# SCH_SEGEMENTOS_MINUTERO_2.net
KiCad netlist of a schematic drawn in Altium Designer
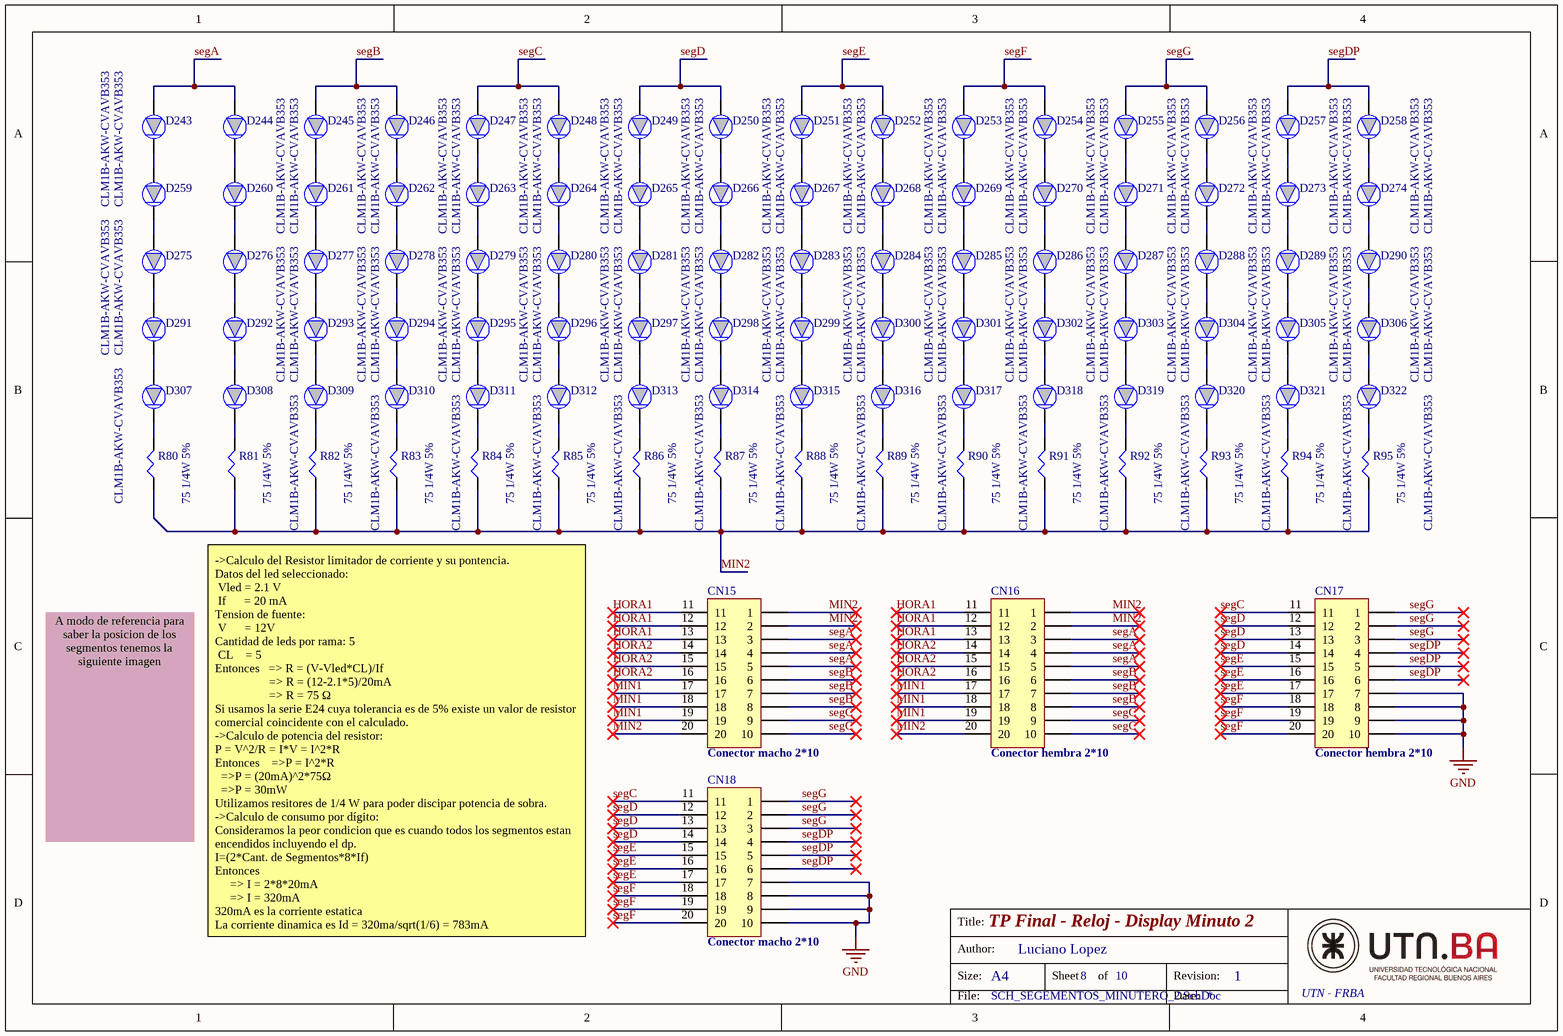
[diagram p0: SCH_SEGEMENTOS_MINUTERO_2.SchDoc]

(export (version "E")
  (design (tool "Eeschema 10.0.6"))
  (components
    (comp (ref "CN15")
      (value "Conector macho 2*10")
      (description "Connector Generic 10 Vias")
      (libsource (lib "SCH_LIB") (part "CONN_2x10P"))
    )
    (comp (ref "CN16")
      (value "Conector hembra 2*10")
      (description "Connector Generic 10 Vias")
      (libsource (lib "SCH_LIB") (part "CONN_2x10P"))
    )
    (comp (ref "CN17")
      (value "Conector hembra 2*10")
      (description "Connector Generic 10 Vias")
      (libsource (lib "SCH_LIB") (part "CONN_2x10P"))
    )
    (comp (ref "CN18")
      (value "Conector macho 2*10")
      (description "Connector Generic 10 Vias")
      (libsource (lib "SCH_LIB") (part "CONN_2x10P"))
    )
    (comp (ref "D243")
      (value "CLM1B-AKW-CVAVB353")
      (footprint "PLCC2_LED")
      (libsource (lib "SCH_LIB") (part "LED_DIODE"))
    )
    (comp (ref "D244")
      (value "CLM1B-AKW-CVAVB353")
      (footprint "PLCC2_LED")
      (libsource (lib "SCH_LIB") (part "LED_DIODE"))
    )
    (comp (ref "D245")
      (value "CLM1B-AKW-CVAVB353")
      (footprint "PLCC2_LED")
      (libsource (lib "SCH_LIB") (part "LED_DIODE"))
    )
    (comp (ref "D246")
      (value "CLM1B-AKW-CVAVB353")
      (footprint "PLCC2_LED")
      (libsource (lib "SCH_LIB") (part "LED_DIODE"))
    )
    (comp (ref "D247")
      (value "CLM1B-AKW-CVAVB353")
      (footprint "PLCC2_LED")
      (libsource (lib "SCH_LIB") (part "LED_DIODE"))
    )
    (comp (ref "D248")
      (value "CLM1B-AKW-CVAVB353")
      (footprint "PLCC2_LED")
      (libsource (lib "SCH_LIB") (part "LED_DIODE"))
    )
    (comp (ref "D249")
      (value "CLM1B-AKW-CVAVB353")
      (footprint "PLCC2_LED")
      (libsource (lib "SCH_LIB") (part "LED_DIODE"))
    )
    (comp (ref "D250")
      (value "CLM1B-AKW-CVAVB353")
      (footprint "PLCC2_LED")
      (libsource (lib "SCH_LIB") (part "LED_DIODE"))
    )
    (comp (ref "D251")
      (value "CLM1B-AKW-CVAVB353")
      (footprint "PLCC2_LED")
      (libsource (lib "SCH_LIB") (part "LED_DIODE"))
    )
    (comp (ref "D252")
      (value "CLM1B-AKW-CVAVB353")
      (footprint "PLCC2_LED")
      (libsource (lib "SCH_LIB") (part "LED_DIODE"))
    )
    (comp (ref "D253")
      (value "CLM1B-AKW-CVAVB353")
      (footprint "PLCC2_LED")
      (libsource (lib "SCH_LIB") (part "LED_DIODE"))
    )
    (comp (ref "D254")
      (value "CLM1B-AKW-CVAVB353")
      (footprint "PLCC2_LED")
      (libsource (lib "SCH_LIB") (part "LED_DIODE"))
    )
    (comp (ref "D255")
      (value "CLM1B-AKW-CVAVB353")
      (footprint "PLCC2_LED")
      (libsource (lib "SCH_LIB") (part "LED_DIODE"))
    )
    (comp (ref "D256")
      (value "CLM1B-AKW-CVAVB353")
      (footprint "PLCC2_LED")
      (libsource (lib "SCH_LIB") (part "LED_DIODE"))
    )
    (comp (ref "D257")
      (value "CLM1B-AKW-CVAVB353")
      (footprint "PLCC2_LED")
      (libsource (lib "SCH_LIB") (part "LED_DIODE"))
    )
    (comp (ref "D258")
      (value "CLM1B-AKW-CVAVB353")
      (footprint "PLCC2_LED")
      (libsource (lib "SCH_LIB") (part "LED_DIODE"))
    )
    (comp (ref "D259")
      (value "CLM1B-AKW-CVAVB353")
      (footprint "PLCC2_LED")
      (libsource (lib "SCH_LIB") (part "LED_DIODE"))
    )
    (comp (ref "D260")
      (value "CLM1B-AKW-CVAVB353")
      (footprint "PLCC2_LED")
      (libsource (lib "SCH_LIB") (part "LED_DIODE"))
    )
    (comp (ref "D261")
      (value "CLM1B-AKW-CVAVB353")
      (footprint "PLCC2_LED")
      (libsource (lib "SCH_LIB") (part "LED_DIODE"))
    )
    (comp (ref "D262")
      (value "CLM1B-AKW-CVAVB353")
      (footprint "PLCC2_LED")
      (libsource (lib "SCH_LIB") (part "LED_DIODE"))
    )
    (comp (ref "D263")
      (value "CLM1B-AKW-CVAVB353")
      (footprint "PLCC2_LED")
      (libsource (lib "SCH_LIB") (part "LED_DIODE"))
    )
    (comp (ref "D264")
      (value "CLM1B-AKW-CVAVB353")
      (footprint "PLCC2_LED")
      (libsource (lib "SCH_LIB") (part "LED_DIODE"))
    )
    (comp (ref "D265")
      (value "CLM1B-AKW-CVAVB353")
      (footprint "PLCC2_LED")
      (libsource (lib "SCH_LIB") (part "LED_DIODE"))
    )
    (comp (ref "D266")
      (value "CLM1B-AKW-CVAVB353")
      (footprint "PLCC2_LED")
      (libsource (lib "SCH_LIB") (part "LED_DIODE"))
    )
    (comp (ref "D267")
      (value "CLM1B-AKW-CVAVB353")
      (footprint "PLCC2_LED")
      (libsource (lib "SCH_LIB") (part "LED_DIODE"))
    )
    (comp (ref "D268")
      (value "CLM1B-AKW-CVAVB353")
      (footprint "PLCC2_LED")
      (libsource (lib "SCH_LIB") (part "LED_DIODE"))
    )
    (comp (ref "D269")
      (value "CLM1B-AKW-CVAVB353")
      (footprint "PLCC2_LED")
      (libsource (lib "SCH_LIB") (part "LED_DIODE"))
    )
    (comp (ref "D270")
      (value "CLM1B-AKW-CVAVB353")
      (footprint "PLCC2_LED")
      (libsource (lib "SCH_LIB") (part "LED_DIODE"))
    )
    (comp (ref "D271")
      (value "CLM1B-AKW-CVAVB353")
      (footprint "PLCC2_LED")
      (libsource (lib "SCH_LIB") (part "LED_DIODE"))
    )
    (comp (ref "D272")
      (value "CLM1B-AKW-CVAVB353")
      (footprint "PLCC2_LED")
      (libsource (lib "SCH_LIB") (part "LED_DIODE"))
    )
    (comp (ref "D273")
      (value "CLM1B-AKW-CVAVB353")
      (footprint "PLCC2_LED")
      (libsource (lib "SCH_LIB") (part "LED_DIODE"))
    )
    (comp (ref "D274")
      (value "CLM1B-AKW-CVAVB353")
      (footprint "PLCC2_LED")
      (libsource (lib "SCH_LIB") (part "LED_DIODE"))
    )
    (comp (ref "D275")
      (value "CLM1B-AKW-CVAVB353")
      (footprint "PLCC2_LED")
      (libsource (lib "SCH_LIB") (part "LED_DIODE"))
    )
    (comp (ref "D276")
      (value "CLM1B-AKW-CVAVB353")
      (footprint "PLCC2_LED")
      (libsource (lib "SCH_LIB") (part "LED_DIODE"))
    )
    (comp (ref "D277")
      (value "CLM1B-AKW-CVAVB353")
      (footprint "PLCC2_LED")
      (libsource (lib "SCH_LIB") (part "LED_DIODE"))
    )
    (comp (ref "D278")
      (value "CLM1B-AKW-CVAVB353")
      (footprint "PLCC2_LED")
      (libsource (lib "SCH_LIB") (part "LED_DIODE"))
    )
    (comp (ref "D279")
      (value "CLM1B-AKW-CVAVB353")
      (footprint "PLCC2_LED")
      (libsource (lib "SCH_LIB") (part "LED_DIODE"))
    )
    (comp (ref "D280")
      (value "CLM1B-AKW-CVAVB353")
      (footprint "PLCC2_LED")
      (libsource (lib "SCH_LIB") (part "LED_DIODE"))
    )
    (comp (ref "D281")
      (value "CLM1B-AKW-CVAVB353")
      (footprint "PLCC2_LED")
      (libsource (lib "SCH_LIB") (part "LED_DIODE"))
    )
    (comp (ref "D282")
      (value "CLM1B-AKW-CVAVB353")
      (footprint "PLCC2_LED")
      (libsource (lib "SCH_LIB") (part "LED_DIODE"))
    )
    (comp (ref "D283")
      (value "CLM1B-AKW-CVAVB353")
      (footprint "PLCC2_LED")
      (libsource (lib "SCH_LIB") (part "LED_DIODE"))
    )
    (comp (ref "D284")
      (value "CLM1B-AKW-CVAVB353")
      (footprint "PLCC2_LED")
      (libsource (lib "SCH_LIB") (part "LED_DIODE"))
    )
    (comp (ref "D285")
      (value "CLM1B-AKW-CVAVB353")
      (footprint "PLCC2_LED")
      (libsource (lib "SCH_LIB") (part "LED_DIODE"))
    )
    (comp (ref "D286")
      (value "CLM1B-AKW-CVAVB353")
      (footprint "PLCC2_LED")
      (libsource (lib "SCH_LIB") (part "LED_DIODE"))
    )
    (comp (ref "D287")
      (value "CLM1B-AKW-CVAVB353")
      (footprint "PLCC2_LED")
      (libsource (lib "SCH_LIB") (part "LED_DIODE"))
    )
    (comp (ref "D288")
      (value "CLM1B-AKW-CVAVB353")
      (footprint "PLCC2_LED")
      (libsource (lib "SCH_LIB") (part "LED_DIODE"))
    )
    (comp (ref "D289")
      (value "CLM1B-AKW-CVAVB353")
      (footprint "PLCC2_LED")
      (libsource (lib "SCH_LIB") (part "LED_DIODE"))
    )
    (comp (ref "D290")
      (value "CLM1B-AKW-CVAVB353")
      (footprint "PLCC2_LED")
      (libsource (lib "SCH_LIB") (part "LED_DIODE"))
    )
    (comp (ref "D291")
      (value "CLM1B-AKW-CVAVB353")
      (footprint "PLCC2_LED")
      (libsource (lib "SCH_LIB") (part "LED_DIODE"))
    )
    (comp (ref "D292")
      (value "CLM1B-AKW-CVAVB353")
      (footprint "PLCC2_LED")
      (libsource (lib "SCH_LIB") (part "LED_DIODE"))
    )
    (comp (ref "D293")
      (value "CLM1B-AKW-CVAVB353")
      (footprint "PLCC2_LED")
      (libsource (lib "SCH_LIB") (part "LED_DIODE"))
    )
    (comp (ref "D294")
      (value "CLM1B-AKW-CVAVB353")
      (footprint "PLCC2_LED")
      (libsource (lib "SCH_LIB") (part "LED_DIODE"))
    )
    (comp (ref "D295")
      (value "CLM1B-AKW-CVAVB353")
      (footprint "PLCC2_LED")
      (libsource (lib "SCH_LIB") (part "LED_DIODE"))
    )
    (comp (ref "D296")
      (value "CLM1B-AKW-CVAVB353")
      (footprint "PLCC2_LED")
      (libsource (lib "SCH_LIB") (part "LED_DIODE"))
    )
    (comp (ref "D297")
      (value "CLM1B-AKW-CVAVB353")
      (footprint "PLCC2_LED")
      (libsource (lib "SCH_LIB") (part "LED_DIODE"))
    )
    (comp (ref "D298")
      (value "CLM1B-AKW-CVAVB353")
      (footprint "PLCC2_LED")
      (libsource (lib "SCH_LIB") (part "LED_DIODE"))
    )
    (comp (ref "D299")
      (value "CLM1B-AKW-CVAVB353")
      (footprint "PLCC2_LED")
      (libsource (lib "SCH_LIB") (part "LED_DIODE"))
    )
    (comp (ref "D300")
      (value "CLM1B-AKW-CVAVB353")
      (footprint "PLCC2_LED")
      (libsource (lib "SCH_LIB") (part "LED_DIODE"))
    )
    (comp (ref "D301")
      (value "CLM1B-AKW-CVAVB353")
      (footprint "PLCC2_LED")
      (libsource (lib "SCH_LIB") (part "LED_DIODE"))
    )
    (comp (ref "D302")
      (value "CLM1B-AKW-CVAVB353")
      (footprint "PLCC2_LED")
      (libsource (lib "SCH_LIB") (part "LED_DIODE"))
    )
    (comp (ref "D303")
      (value "CLM1B-AKW-CVAVB353")
      (footprint "PLCC2_LED")
      (libsource (lib "SCH_LIB") (part "LED_DIODE"))
    )
    (comp (ref "D304")
      (value "CLM1B-AKW-CVAVB353")
      (footprint "PLCC2_LED")
      (libsource (lib "SCH_LIB") (part "LED_DIODE"))
    )
    (comp (ref "D305")
      (value "CLM1B-AKW-CVAVB353")
      (footprint "PLCC2_LED")
      (libsource (lib "SCH_LIB") (part "LED_DIODE"))
    )
    (comp (ref "D306")
      (value "CLM1B-AKW-CVAVB353")
      (footprint "PLCC2_LED")
      (libsource (lib "SCH_LIB") (part "LED_DIODE"))
    )
    (comp (ref "D307")
      (value "CLM1B-AKW-CVAVB353")
      (footprint "PLCC2_LED")
      (libsource (lib "SCH_LIB") (part "LED_DIODE"))
    )
    (comp (ref "D308")
      (value "CLM1B-AKW-CVAVB353")
      (footprint "PLCC2_LED")
      (libsource (lib "SCH_LIB") (part "LED_DIODE"))
    )
    (comp (ref "D309")
      (value "CLM1B-AKW-CVAVB353")
      (footprint "PLCC2_LED")
      (libsource (lib "SCH_LIB") (part "LED_DIODE"))
    )
    (comp (ref "D310")
      (value "CLM1B-AKW-CVAVB353")
      (footprint "PLCC2_LED")
      (libsource (lib "SCH_LIB") (part "LED_DIODE"))
    )
    (comp (ref "D311")
      (value "CLM1B-AKW-CVAVB353")
      (footprint "PLCC2_LED")
      (libsource (lib "SCH_LIB") (part "LED_DIODE"))
    )
    (comp (ref "D312")
      (value "CLM1B-AKW-CVAVB353")
      (footprint "PLCC2_LED")
      (libsource (lib "SCH_LIB") (part "LED_DIODE"))
    )
    (comp (ref "D313")
      (value "CLM1B-AKW-CVAVB353")
      (footprint "PLCC2_LED")
      (libsource (lib "SCH_LIB") (part "LED_DIODE"))
    )
    (comp (ref "D314")
      (value "CLM1B-AKW-CVAVB353")
      (footprint "PLCC2_LED")
      (libsource (lib "SCH_LIB") (part "LED_DIODE"))
    )
    (comp (ref "D315")
      (value "CLM1B-AKW-CVAVB353")
      (footprint "PLCC2_LED")
      (libsource (lib "SCH_LIB") (part "LED_DIODE"))
    )
    (comp (ref "D316")
      (value "CLM1B-AKW-CVAVB353")
      (footprint "PLCC2_LED")
      (libsource (lib "SCH_LIB") (part "LED_DIODE"))
    )
    (comp (ref "D317")
      (value "CLM1B-AKW-CVAVB353")
      (footprint "PLCC2_LED")
      (libsource (lib "SCH_LIB") (part "LED_DIODE"))
    )
    (comp (ref "D318")
      (value "CLM1B-AKW-CVAVB353")
      (footprint "PLCC2_LED")
      (libsource (lib "SCH_LIB") (part "LED_DIODE"))
    )
    (comp (ref "D319")
      (value "CLM1B-AKW-CVAVB353")
      (footprint "PLCC2_LED")
      (libsource (lib "SCH_LIB") (part "LED_DIODE"))
    )
    (comp (ref "D320")
      (value "CLM1B-AKW-CVAVB353")
      (footprint "PLCC2_LED")
      (libsource (lib "SCH_LIB") (part "LED_DIODE"))
    )
    (comp (ref "D321")
      (value "CLM1B-AKW-CVAVB353")
      (footprint "PLCC2_LED")
      (libsource (lib "SCH_LIB") (part "LED_DIODE"))
    )
    (comp (ref "D322")
      (value "CLM1B-AKW-CVAVB353")
      (footprint "PLCC2_LED")
      (libsource (lib "SCH_LIB") (part "LED_DIODE"))
    )
    (comp (ref "R80") (value "75 1/4W 5%") (footprint "R_0805") (libsource (lib "SCH_LIB") (part "Resistor")))
    (comp (ref "R81") (value "75 1/4W 5%") (footprint "R_0805") (libsource (lib "SCH_LIB") (part "Resistor")))
    (comp (ref "R82") (value "75 1/4W 5%") (footprint "R_0805") (libsource (lib "SCH_LIB") (part "Resistor")))
    (comp (ref "R83") (value "75 1/4W 5%") (footprint "R_0805") (libsource (lib "SCH_LIB") (part "Resistor")))
    (comp (ref "R84") (value "75 1/4W 5%") (footprint "R_0805") (libsource (lib "SCH_LIB") (part "Resistor")))
    (comp (ref "R85") (value "75 1/4W 5%") (footprint "R_0805") (libsource (lib "SCH_LIB") (part "Resistor")))
    (comp (ref "R86") (value "75 1/4W 5%") (footprint "R_0805") (libsource (lib "SCH_LIB") (part "Resistor")))
    (comp (ref "R87") (value "75 1/4W 5%") (footprint "R_0805") (libsource (lib "SCH_LIB") (part "Resistor")))
    (comp (ref "R88") (value "75 1/4W 5%") (footprint "R_0805") (libsource (lib "SCH_LIB") (part "Resistor")))
    (comp (ref "R89") (value "75 1/4W 5%") (footprint "R_0805") (libsource (lib "SCH_LIB") (part "Resistor")))
    (comp (ref "R90") (value "75 1/4W 5%") (footprint "R_0805") (libsource (lib "SCH_LIB") (part "Resistor")))
    (comp (ref "R91") (value "75 1/4W 5%") (footprint "R_0805") (libsource (lib "SCH_LIB") (part "Resistor")))
    (comp (ref "R92") (value "75 1/4W 5%") (footprint "R_0805") (libsource (lib "SCH_LIB") (part "Resistor")))
    (comp (ref "R93") (value "75 1/4W 5%") (footprint "R_0805") (libsource (lib "SCH_LIB") (part "Resistor")))
    (comp (ref "R94") (value "75 1/4W 5%") (footprint "R_0805") (libsource (lib "SCH_LIB") (part "Resistor")))
    (comp (ref "R95") (value "75 1/4W 5%") (footprint "R_0805") (libsource (lib "SCH_LIB") (part "Resistor")))
  )
  (nets
    (net (code "1") (name "/HORA1") (class "Default")
      (node (ref "CN15") (pin "11") (pinfunction "11_11") (pintype "passive"))
      (node (ref "CN15") (pin "12") (pinfunction "12_12") (pintype "passive"))
      (node (ref "CN15") (pin "13") (pinfunction "13_13") (pintype "passive"))
      (node (ref "CN16") (pin "11") (pinfunction "11_11") (pintype "passive"))
      (node (ref "CN16") (pin "12") (pinfunction "12_12") (pintype "passive"))
      (node (ref "CN16") (pin "13") (pinfunction "13_13") (pintype "passive"))
    )
    (net (code "2") (name "/HORA2") (class "Default")
      (node (ref "CN15") (pin "14") (pinfunction "14_14") (pintype "passive"))
      (node (ref "CN15") (pin "15") (pinfunction "15_15") (pintype "passive"))
      (node (ref "CN15") (pin "16") (pinfunction "16_16") (pintype "passive"))
      (node (ref "CN16") (pin "14") (pinfunction "14_14") (pintype "passive"))
      (node (ref "CN16") (pin "15") (pinfunction "15_15") (pintype "passive"))
      (node (ref "CN16") (pin "16") (pinfunction "16_16") (pintype "passive"))
    )
    (net (code "3") (name "/MIN1") (class "Default")
      (node (ref "CN15") (pin "17") (pinfunction "17_17") (pintype "passive"))
      (node (ref "CN15") (pin "18") (pinfunction "18_18") (pintype "passive"))
      (node (ref "CN15") (pin "19") (pinfunction "19_19") (pintype "passive"))
      (node (ref "CN16") (pin "17") (pinfunction "17_17") (pintype "passive"))
      (node (ref "CN16") (pin "18") (pinfunction "18_18") (pintype "passive"))
      (node (ref "CN16") (pin "19") (pinfunction "19_19") (pintype "passive"))
    )
    (net (code "4") (name "/MIN2") (class "Default")
      (node (ref "CN15") (pin "1") (pinfunction "1_1") (pintype "passive"))
      (node (ref "CN15") (pin "2") (pinfunction "2_2") (pintype "passive"))
      (node (ref "CN15") (pin "20") (pinfunction "20_20") (pintype "passive"))
      (node (ref "CN16") (pin "1") (pinfunction "1_1") (pintype "passive"))
      (node (ref "CN16") (pin "2") (pinfunction "2_2") (pintype "passive"))
      (node (ref "CN16") (pin "20") (pinfunction "20_20") (pintype "passive"))
      (node (ref "R80") (pin "47") (pinfunction "47_47") (pintype "passive"))
      (node (ref "R81") (pin "47") (pinfunction "47_47") (pintype "passive"))
      (node (ref "R82") (pin "47") (pinfunction "47_47") (pintype "passive"))
      (node (ref "R83") (pin "47") (pinfunction "47_47") (pintype "passive"))
      (node (ref "R84") (pin "47") (pinfunction "47_47") (pintype "passive"))
      (node (ref "R85") (pin "47") (pinfunction "47_47") (pintype "passive"))
      (node (ref "R86") (pin "47") (pinfunction "47_47") (pintype "passive"))
      (node (ref "R87") (pin "47") (pinfunction "47_47") (pintype "passive"))
      (node (ref "R88") (pin "47") (pinfunction "47_47") (pintype "passive"))
      (node (ref "R89") (pin "47") (pinfunction "47_47") (pintype "passive"))
      (node (ref "R90") (pin "47") (pinfunction "47_47") (pintype "passive"))
      (node (ref "R91") (pin "47") (pinfunction "47_47") (pintype "passive"))
      (node (ref "R92") (pin "47") (pinfunction "47_47") (pintype "passive"))
      (node (ref "R93") (pin "47") (pinfunction "47_47") (pintype "passive"))
      (node (ref "R94") (pin "47") (pinfunction "47_47") (pintype "passive"))
      (node (ref "R95") (pin "47") (pinfunction "47_47") (pintype "passive"))
    )
    (net (code "5") (name "/segA") (class "Default")
      (node (ref "CN15") (pin "3") (pinfunction "3_3") (pintype "passive"))
      (node (ref "CN15") (pin "4") (pinfunction "4_4") (pintype "passive"))
      (node (ref "CN15") (pin "5") (pinfunction "5_5") (pintype "passive"))
      (node (ref "CN16") (pin "3") (pinfunction "3_3") (pintype "passive"))
      (node (ref "CN16") (pin "4") (pinfunction "4_4") (pintype "passive"))
      (node (ref "CN16") (pin "5") (pinfunction "5_5") (pintype "passive"))
      (node (ref "D243") (pin "12") (pinfunction "12_12") (pintype "passive"))
      (node (ref "D244") (pin "12") (pinfunction "12_12") (pintype "passive"))
    )
    (net (code "6") (name "/segB") (class "Default")
      (node (ref "CN15") (pin "6") (pinfunction "6_6") (pintype "passive"))
      (node (ref "CN15") (pin "7") (pinfunction "7_7") (pintype "passive"))
      (node (ref "CN15") (pin "8") (pinfunction "8_8") (pintype "passive"))
      (node (ref "CN16") (pin "6") (pinfunction "6_6") (pintype "passive"))
      (node (ref "CN16") (pin "7") (pinfunction "7_7") (pintype "passive"))
      (node (ref "CN16") (pin "8") (pinfunction "8_8") (pintype "passive"))
      (node (ref "D245") (pin "12") (pinfunction "12_12") (pintype "passive"))
      (node (ref "D246") (pin "12") (pinfunction "12_12") (pintype "passive"))
    )
    (net (code "7") (name "/segC") (class "Default")
      (node (ref "CN15") (pin "10") (pinfunction "10_10") (pintype "passive"))
      (node (ref "CN15") (pin "9") (pinfunction "9_9") (pintype "passive"))
      (node (ref "CN16") (pin "10") (pinfunction "10_10") (pintype "passive"))
      (node (ref "CN16") (pin "9") (pinfunction "9_9") (pintype "passive"))
      (node (ref "CN17") (pin "11") (pinfunction "11_11") (pintype "passive"))
      (node (ref "CN18") (pin "11") (pinfunction "11_11") (pintype "passive"))
      (node (ref "D247") (pin "12") (pinfunction "12_12") (pintype "passive"))
      (node (ref "D248") (pin "12") (pinfunction "12_12") (pintype "passive"))
    )
    (net (code "8") (name "/segD") (class "Default")
      (node (ref "CN17") (pin "12") (pinfunction "12_12") (pintype "passive"))
      (node (ref "CN17") (pin "13") (pinfunction "13_13") (pintype "passive"))
      (node (ref "CN17") (pin "14") (pinfunction "14_14") (pintype "passive"))
      (node (ref "CN18") (pin "12") (pinfunction "12_12") (pintype "passive"))
      (node (ref "CN18") (pin "13") (pinfunction "13_13") (pintype "passive"))
      (node (ref "CN18") (pin "14") (pinfunction "14_14") (pintype "passive"))
      (node (ref "D249") (pin "12") (pinfunction "12_12") (pintype "passive"))
      (node (ref "D250") (pin "12") (pinfunction "12_12") (pintype "passive"))
    )
    (net (code "9") (name "/segDP") (class "Default")
      (node (ref "CN17") (pin "4") (pinfunction "4_4") (pintype "passive"))
      (node (ref "CN17") (pin "5") (pinfunction "5_5") (pintype "passive"))
      (node (ref "CN17") (pin "6") (pinfunction "6_6") (pintype "passive"))
      (node (ref "CN18") (pin "4") (pinfunction "4_4") (pintype "passive"))
      (node (ref "CN18") (pin "5") (pinfunction "5_5") (pintype "passive"))
      (node (ref "CN18") (pin "6") (pinfunction "6_6") (pintype "passive"))
      (node (ref "D257") (pin "12") (pinfunction "12_12") (pintype "passive"))
      (node (ref "D258") (pin "12") (pinfunction "12_12") (pintype "passive"))
    )
    (net (code "10") (name "/segE") (class "Default")
      (node (ref "CN17") (pin "15") (pinfunction "15_15") (pintype "passive"))
      (node (ref "CN17") (pin "16") (pinfunction "16_16") (pintype "passive"))
      (node (ref "CN17") (pin "17") (pinfunction "17_17") (pintype "passive"))
      (node (ref "CN18") (pin "15") (pinfunction "15_15") (pintype "passive"))
      (node (ref "CN18") (pin "16") (pinfunction "16_16") (pintype "passive"))
      (node (ref "CN18") (pin "17") (pinfunction "17_17") (pintype "passive"))
      (node (ref "D251") (pin "12") (pinfunction "12_12") (pintype "passive"))
      (node (ref "D252") (pin "12") (pinfunction "12_12") (pintype "passive"))
    )
    (net (code "11") (name "/segF") (class "Default")
      (node (ref "CN17") (pin "18") (pinfunction "18_18") (pintype "passive"))
      (node (ref "CN17") (pin "19") (pinfunction "19_19") (pintype "passive"))
      (node (ref "CN17") (pin "20") (pinfunction "20_20") (pintype "passive"))
      (node (ref "CN18") (pin "18") (pinfunction "18_18") (pintype "passive"))
      (node (ref "CN18") (pin "19") (pinfunction "19_19") (pintype "passive"))
      (node (ref "CN18") (pin "20") (pinfunction "20_20") (pintype "passive"))
      (node (ref "D253") (pin "12") (pinfunction "12_12") (pintype "passive"))
      (node (ref "D254") (pin "12") (pinfunction "12_12") (pintype "passive"))
    )
    (net (code "12") (name "/segG") (class "Default")
      (node (ref "CN17") (pin "1") (pinfunction "1_1") (pintype "passive"))
      (node (ref "CN17") (pin "2") (pinfunction "2_2") (pintype "passive"))
      (node (ref "CN17") (pin "3") (pinfunction "3_3") (pintype "passive"))
      (node (ref "CN18") (pin "1") (pinfunction "1_1") (pintype "passive"))
      (node (ref "CN18") (pin "2") (pinfunction "2_2") (pintype "passive"))
      (node (ref "CN18") (pin "3") (pinfunction "3_3") (pintype "passive"))
      (node (ref "D255") (pin "12") (pinfunction "12_12") (pintype "passive"))
      (node (ref "D256") (pin "12") (pinfunction "12_12") (pintype "passive"))
    )
    (net (code "13") (name "GND") (class "Default")
      (node (ref "CN17") (pin "10") (pinfunction "10_10") (pintype "passive"))
      (node (ref "CN17") (pin "7") (pinfunction "7_7") (pintype "passive"))
      (node (ref "CN17") (pin "8") (pinfunction "8_8") (pintype "passive"))
      (node (ref "CN17") (pin "9") (pinfunction "9_9") (pintype "passive"))
      (node (ref "CN18") (pin "10") (pinfunction "10_10") (pintype "passive"))
      (node (ref "CN18") (pin "7") (pinfunction "7_7") (pintype "passive"))
      (node (ref "CN18") (pin "8") (pinfunction "8_8") (pintype "passive"))
      (node (ref "CN18") (pin "9") (pinfunction "9_9") (pintype "passive"))
    )
    (net (code "14") (name "Net-(D243-Pad11)") (class "Default")
      (node (ref "D243") (pin "11") (pinfunction "11_11") (pintype "passive"))
      (node (ref "D259") (pin "12") (pinfunction "12_12") (pintype "passive"))
    )
    (net (code "15") (name "Net-(D244-Pad11)") (class "Default")
      (node (ref "D244") (pin "11") (pinfunction "11_11") (pintype "passive"))
      (node (ref "D260") (pin "12") (pinfunction "12_12") (pintype "passive"))
    )
    (net (code "16") (name "Net-(D245-Pad11)") (class "Default")
      (node (ref "D245") (pin "11") (pinfunction "11_11") (pintype "passive"))
      (node (ref "D261") (pin "12") (pinfunction "12_12") (pintype "passive"))
    )
    (net (code "17") (name "Net-(D246-Pad11)") (class "Default")
      (node (ref "D246") (pin "11") (pinfunction "11_11") (pintype "passive"))
      (node (ref "D262") (pin "12") (pinfunction "12_12") (pintype "passive"))
    )
    (net (code "18") (name "Net-(D247-Pad11)") (class "Default")
      (node (ref "D247") (pin "11") (pinfunction "11_11") (pintype "passive"))
      (node (ref "D263") (pin "12") (pinfunction "12_12") (pintype "passive"))
    )
    (net (code "19") (name "Net-(D248-Pad11)") (class "Default")
      (node (ref "D248") (pin "11") (pinfunction "11_11") (pintype "passive"))
      (node (ref "D264") (pin "12") (pinfunction "12_12") (pintype "passive"))
    )
    (net (code "20") (name "Net-(D249-Pad11)") (class "Default")
      (node (ref "D249") (pin "11") (pinfunction "11_11") (pintype "passive"))
      (node (ref "D265") (pin "12") (pinfunction "12_12") (pintype "passive"))
    )
    (net (code "21") (name "Net-(D250-Pad11)") (class "Default")
      (node (ref "D250") (pin "11") (pinfunction "11_11") (pintype "passive"))
      (node (ref "D266") (pin "12") (pinfunction "12_12") (pintype "passive"))
    )
    (net (code "22") (name "Net-(D251-Pad11)") (class "Default")
      (node (ref "D251") (pin "11") (pinfunction "11_11") (pintype "passive"))
      (node (ref "D267") (pin "12") (pinfunction "12_12") (pintype "passive"))
    )
    (net (code "23") (name "Net-(D252-Pad11)") (class "Default")
      (node (ref "D252") (pin "11") (pinfunction "11_11") (pintype "passive"))
      (node (ref "D268") (pin "12") (pinfunction "12_12") (pintype "passive"))
    )
    (net (code "24") (name "Net-(D253-Pad11)") (class "Default")
      (node (ref "D253") (pin "11") (pinfunction "11_11") (pintype "passive"))
      (node (ref "D269") (pin "12") (pinfunction "12_12") (pintype "passive"))
    )
    (net (code "25") (name "Net-(D254-Pad11)") (class "Default")
      (node (ref "D254") (pin "11") (pinfunction "11_11") (pintype "passive"))
      (node (ref "D270") (pin "12") (pinfunction "12_12") (pintype "passive"))
    )
    (net (code "26") (name "Net-(D255-Pad11)") (class "Default")
      (node (ref "D255") (pin "11") (pinfunction "11_11") (pintype "passive"))
      (node (ref "D271") (pin "12") (pinfunction "12_12") (pintype "passive"))
    )
    (net (code "27") (name "Net-(D256-Pad11)") (class "Default")
      (node (ref "D256") (pin "11") (pinfunction "11_11") (pintype "passive"))
      (node (ref "D272") (pin "12") (pinfunction "12_12") (pintype "passive"))
    )
    (net (code "28") (name "Net-(D257-Pad11)") (class "Default")
      (node (ref "D257") (pin "11") (pinfunction "11_11") (pintype "passive"))
      (node (ref "D273") (pin "12") (pinfunction "12_12") (pintype "passive"))
    )
    (net (code "29") (name "Net-(D258-Pad11)") (class "Default")
      (node (ref "D258") (pin "11") (pinfunction "11_11") (pintype "passive"))
      (node (ref "D274") (pin "12") (pinfunction "12_12") (pintype "passive"))
    )
    (net (code "30") (name "Net-(D259-Pad11)") (class "Default")
      (node (ref "D259") (pin "11") (pinfunction "11_11") (pintype "passive"))
      (node (ref "D275") (pin "12") (pinfunction "12_12") (pintype "passive"))
    )
    (net (code "31") (name "Net-(D260-Pad11)") (class "Default")
      (node (ref "D260") (pin "11") (pinfunction "11_11") (pintype "passive"))
      (node (ref "D276") (pin "12") (pinfunction "12_12") (pintype "passive"))
    )
    (net (code "32") (name "Net-(D261-Pad11)") (class "Default")
      (node (ref "D261") (pin "11") (pinfunction "11_11") (pintype "passive"))
      (node (ref "D277") (pin "12") (pinfunction "12_12") (pintype "passive"))
    )
    (net (code "33") (name "Net-(D262-Pad11)") (class "Default")
      (node (ref "D262") (pin "11") (pinfunction "11_11") (pintype "passive"))
      (node (ref "D278") (pin "12") (pinfunction "12_12") (pintype "passive"))
    )
    (net (code "34") (name "Net-(D263-Pad11)") (class "Default")
      (node (ref "D263") (pin "11") (pinfunction "11_11") (pintype "passive"))
      (node (ref "D279") (pin "12") (pinfunction "12_12") (pintype "passive"))
    )
    (net (code "35") (name "Net-(D264-Pad11)") (class "Default")
      (node (ref "D264") (pin "11") (pinfunction "11_11") (pintype "passive"))
      (node (ref "D280") (pin "12") (pinfunction "12_12") (pintype "passive"))
    )
    (net (code "36") (name "Net-(D265-Pad11)") (class "Default")
      (node (ref "D265") (pin "11") (pinfunction "11_11") (pintype "passive"))
      (node (ref "D281") (pin "12") (pinfunction "12_12") (pintype "passive"))
    )
    (net (code "37") (name "Net-(D266-Pad11)") (class "Default")
      (node (ref "D266") (pin "11") (pinfunction "11_11") (pintype "passive"))
      (node (ref "D282") (pin "12") (pinfunction "12_12") (pintype "passive"))
    )
    (net (code "38") (name "Net-(D267-Pad11)") (class "Default")
      (node (ref "D267") (pin "11") (pinfunction "11_11") (pintype "passive"))
      (node (ref "D283") (pin "12") (pinfunction "12_12") (pintype "passive"))
    )
    (net (code "39") (name "Net-(D268-Pad11)") (class "Default")
      (node (ref "D268") (pin "11") (pinfunction "11_11") (pintype "passive"))
      (node (ref "D284") (pin "12") (pinfunction "12_12") (pintype "passive"))
    )
    (net (code "40") (name "Net-(D269-Pad11)") (class "Default")
      (node (ref "D269") (pin "11") (pinfunction "11_11") (pintype "passive"))
      (node (ref "D285") (pin "12") (pinfunction "12_12") (pintype "passive"))
    )
    (net (code "41") (name "Net-(D270-Pad11)") (class "Default")
      (node (ref "D270") (pin "11") (pinfunction "11_11") (pintype "passive"))
      (node (ref "D286") (pin "12") (pinfunction "12_12") (pintype "passive"))
    )
    (net (code "42") (name "Net-(D271-Pad11)") (class "Default")
      (node (ref "D271") (pin "11") (pinfunction "11_11") (pintype "passive"))
      (node (ref "D287") (pin "12") (pinfunction "12_12") (pintype "passive"))
    )
    (net (code "43") (name "Net-(D272-Pad11)") (class "Default")
      (node (ref "D272") (pin "11") (pinfunction "11_11") (pintype "passive"))
      (node (ref "D288") (pin "12") (pinfunction "12_12") (pintype "passive"))
    )
    (net (code "44") (name "Net-(D273-Pad11)") (class "Default")
      (node (ref "D273") (pin "11") (pinfunction "11_11") (pintype "passive"))
      (node (ref "D289") (pin "12") (pinfunction "12_12") (pintype "passive"))
    )
    (net (code "45") (name "Net-(D274-Pad11)") (class "Default")
      (node (ref "D274") (pin "11") (pinfunction "11_11") (pintype "passive"))
      (node (ref "D290") (pin "12") (pinfunction "12_12") (pintype "passive"))
    )
    (net (code "46") (name "Net-(D275-Pad11)") (class "Default")
      (node (ref "D275") (pin "11") (pinfunction "11_11") (pintype "passive"))
      (node (ref "D291") (pin "12") (pinfunction "12_12") (pintype "passive"))
    )
    (net (code "47") (name "Net-(D276-Pad11)") (class "Default")
      (node (ref "D276") (pin "11") (pinfunction "11_11") (pintype "passive"))
      (node (ref "D292") (pin "12") (pinfunction "12_12") (pintype "passive"))
    )
    (net (code "48") (name "Net-(D277-Pad11)") (class "Default")
      (node (ref "D277") (pin "11") (pinfunction "11_11") (pintype "passive"))
      (node (ref "D293") (pin "12") (pinfunction "12_12") (pintype "passive"))
    )
    (net (code "49") (name "Net-(D278-Pad11)") (class "Default")
      (node (ref "D278") (pin "11") (pinfunction "11_11") (pintype "passive"))
      (node (ref "D294") (pin "12") (pinfunction "12_12") (pintype "passive"))
    )
    (net (code "50") (name "Net-(D279-Pad11)") (class "Default")
      (node (ref "D279") (pin "11") (pinfunction "11_11") (pintype "passive"))
      (node (ref "D295") (pin "12") (pinfunction "12_12") (pintype "passive"))
    )
    (net (code "51") (name "Net-(D280-Pad11)") (class "Default")
      (node (ref "D280") (pin "11") (pinfunction "11_11") (pintype "passive"))
      (node (ref "D296") (pin "12") (pinfunction "12_12") (pintype "passive"))
    )
    (net (code "52") (name "Net-(D281-Pad11)") (class "Default")
      (node (ref "D281") (pin "11") (pinfunction "11_11") (pintype "passive"))
      (node (ref "D297") (pin "12") (pinfunction "12_12") (pintype "passive"))
    )
    (net (code "53") (name "Net-(D282-Pad11)") (class "Default")
      (node (ref "D282") (pin "11") (pinfunction "11_11") (pintype "passive"))
      (node (ref "D298") (pin "12") (pinfunction "12_12") (pintype "passive"))
    )
    (net (code "54") (name "Net-(D283-Pad11)") (class "Default")
      (node (ref "D283") (pin "11") (pinfunction "11_11") (pintype "passive"))
      (node (ref "D299") (pin "12") (pinfunction "12_12") (pintype "passive"))
    )
    (net (code "55") (name "Net-(D284-Pad11)") (class "Default")
      (node (ref "D284") (pin "11") (pinfunction "11_11") (pintype "passive"))
      (node (ref "D300") (pin "12") (pinfunction "12_12") (pintype "passive"))
    )
    (net (code "56") (name "Net-(D285-Pad11)") (class "Default")
      (node (ref "D285") (pin "11") (pinfunction "11_11") (pintype "passive"))
      (node (ref "D301") (pin "12") (pinfunction "12_12") (pintype "passive"))
    )
    (net (code "57") (name "Net-(D286-Pad11)") (class "Default")
      (node (ref "D286") (pin "11") (pinfunction "11_11") (pintype "passive"))
      (node (ref "D302") (pin "12") (pinfunction "12_12") (pintype "passive"))
    )
    (net (code "58") (name "Net-(D287-Pad11)") (class "Default")
      (node (ref "D287") (pin "11") (pinfunction "11_11") (pintype "passive"))
      (node (ref "D303") (pin "12") (pinfunction "12_12") (pintype "passive"))
    )
    (net (code "59") (name "Net-(D288-Pad11)") (class "Default")
      (node (ref "D288") (pin "11") (pinfunction "11_11") (pintype "passive"))
      (node (ref "D304") (pin "12") (pinfunction "12_12") (pintype "passive"))
    )
    (net (code "60") (name "Net-(D289-Pad11)") (class "Default")
      (node (ref "D289") (pin "11") (pinfunction "11_11") (pintype "passive"))
      (node (ref "D305") (pin "12") (pinfunction "12_12") (pintype "passive"))
    )
    (net (code "61") (name "Net-(D290-Pad11)") (class "Default")
      (node (ref "D290") (pin "11") (pinfunction "11_11") (pintype "passive"))
      (node (ref "D306") (pin "12") (pinfunction "12_12") (pintype "passive"))
    )
    (net (code "62") (name "Net-(D291-Pad11)") (class "Default")
      (node (ref "D291") (pin "11") (pinfunction "11_11") (pintype "passive"))
      (node (ref "D307") (pin "12") (pinfunction "12_12") (pintype "passive"))
    )
    (net (code "63") (name "Net-(D292-Pad11)") (class "Default")
      (node (ref "D292") (pin "11") (pinfunction "11_11") (pintype "passive"))
      (node (ref "D308") (pin "12") (pinfunction "12_12") (pintype "passive"))
    )
    (net (code "64") (name "Net-(D293-Pad11)") (class "Default")
      (node (ref "D293") (pin "11") (pinfunction "11_11") (pintype "passive"))
      (node (ref "D309") (pin "12") (pinfunction "12_12") (pintype "passive"))
    )
    (net (code "65") (name "Net-(D294-Pad11)") (class "Default")
      (node (ref "D294") (pin "11") (pinfunction "11_11") (pintype "passive"))
      (node (ref "D310") (pin "12") (pinfunction "12_12") (pintype "passive"))
    )
    (net (code "66") (name "Net-(D295-Pad11)") (class "Default")
      (node (ref "D295") (pin "11") (pinfunction "11_11") (pintype "passive"))
      (node (ref "D311") (pin "12") (pinfunction "12_12") (pintype "passive"))
    )
    (net (code "67") (name "Net-(D296-Pad11)") (class "Default")
      (node (ref "D296") (pin "11") (pinfunction "11_11") (pintype "passive"))
      (node (ref "D312") (pin "12") (pinfunction "12_12") (pintype "passive"))
    )
    (net (code "68") (name "Net-(D297-Pad11)") (class "Default")
      (node (ref "D297") (pin "11") (pinfunction "11_11") (pintype "passive"))
      (node (ref "D313") (pin "12") (pinfunction "12_12") (pintype "passive"))
    )
    (net (code "69") (name "Net-(D298-Pad11)") (class "Default")
      (node (ref "D298") (pin "11") (pinfunction "11_11") (pintype "passive"))
      (node (ref "D314") (pin "12") (pinfunction "12_12") (pintype "passive"))
    )
    (net (code "70") (name "Net-(D299-Pad11)") (class "Default")
      (node (ref "D299") (pin "11") (pinfunction "11_11") (pintype "passive"))
      (node (ref "D315") (pin "12") (pinfunction "12_12") (pintype "passive"))
    )
    (net (code "71") (name "Net-(D300-Pad11)") (class "Default")
      (node (ref "D300") (pin "11") (pinfunction "11_11") (pintype "passive"))
      (node (ref "D316") (pin "12") (pinfunction "12_12") (pintype "passive"))
    )
    (net (code "72") (name "Net-(D301-Pad11)") (class "Default")
      (node (ref "D301") (pin "11") (pinfunction "11_11") (pintype "passive"))
      (node (ref "D317") (pin "12") (pinfunction "12_12") (pintype "passive"))
    )
    (net (code "73") (name "Net-(D302-Pad11)") (class "Default")
      (node (ref "D302") (pin "11") (pinfunction "11_11") (pintype "passive"))
      (node (ref "D318") (pin "12") (pinfunction "12_12") (pintype "passive"))
    )
    (net (code "74") (name "Net-(D303-Pad11)") (class "Default")
      (node (ref "D303") (pin "11") (pinfunction "11_11") (pintype "passive"))
      (node (ref "D319") (pin "12") (pinfunction "12_12") (pintype "passive"))
    )
    (net (code "75") (name "Net-(D304-Pad11)") (class "Default")
      (node (ref "D304") (pin "11") (pinfunction "11_11") (pintype "passive"))
      (node (ref "D320") (pin "12") (pinfunction "12_12") (pintype "passive"))
    )
    (net (code "76") (name "Net-(D305-Pad11)") (class "Default")
      (node (ref "D305") (pin "11") (pinfunction "11_11") (pintype "passive"))
      (node (ref "D321") (pin "12") (pinfunction "12_12") (pintype "passive"))
    )
    (net (code "77") (name "Net-(D306-Pad11)") (class "Default")
      (node (ref "D306") (pin "11") (pinfunction "11_11") (pintype "passive"))
      (node (ref "D322") (pin "12") (pinfunction "12_12") (pintype "passive"))
    )
    (net (code "78") (name "Net-(D307-Pad11)") (class "Default")
      (node (ref "D307") (pin "11") (pinfunction "11_11") (pintype "passive"))
      (node (ref "R80") (pin "48") (pinfunction "48_48") (pintype "passive"))
    )
    (net (code "79") (name "Net-(D308-Pad11)") (class "Default")
      (node (ref "D308") (pin "11") (pinfunction "11_11") (pintype "passive"))
      (node (ref "R81") (pin "48") (pinfunction "48_48") (pintype "passive"))
    )
    (net (code "80") (name "Net-(D309-Pad11)") (class "Default")
      (node (ref "D309") (pin "11") (pinfunction "11_11") (pintype "passive"))
      (node (ref "R82") (pin "48") (pinfunction "48_48") (pintype "passive"))
    )
    (net (code "81") (name "Net-(D310-Pad11)") (class "Default")
      (node (ref "D310") (pin "11") (pinfunction "11_11") (pintype "passive"))
      (node (ref "R83") (pin "48") (pinfunction "48_48") (pintype "passive"))
    )
    (net (code "82") (name "Net-(D311-Pad11)") (class "Default")
      (node (ref "D311") (pin "11") (pinfunction "11_11") (pintype "passive"))
      (node (ref "R84") (pin "48") (pinfunction "48_48") (pintype "passive"))
    )
    (net (code "83") (name "Net-(D312-Pad11)") (class "Default")
      (node (ref "D312") (pin "11") (pinfunction "11_11") (pintype "passive"))
      (node (ref "R85") (pin "48") (pinfunction "48_48") (pintype "passive"))
    )
    (net (code "84") (name "Net-(D313-Pad11)") (class "Default")
      (node (ref "D313") (pin "11") (pinfunction "11_11") (pintype "passive"))
      (node (ref "R86") (pin "48") (pinfunction "48_48") (pintype "passive"))
    )
    (net (code "85") (name "Net-(D314-Pad11)") (class "Default")
      (node (ref "D314") (pin "11") (pinfunction "11_11") (pintype "passive"))
      (node (ref "R87") (pin "48") (pinfunction "48_48") (pintype "passive"))
    )
    (net (code "86") (name "Net-(D315-Pad11)") (class "Default")
      (node (ref "D315") (pin "11") (pinfunction "11_11") (pintype "passive"))
      (node (ref "R88") (pin "48") (pinfunction "48_48") (pintype "passive"))
    )
    (net (code "87") (name "Net-(D316-Pad11)") (class "Default")
      (node (ref "D316") (pin "11") (pinfunction "11_11") (pintype "passive"))
      (node (ref "R89") (pin "48") (pinfunction "48_48") (pintype "passive"))
    )
    (net (code "88") (name "Net-(D317-Pad11)") (class "Default")
      (node (ref "D317") (pin "11") (pinfunction "11_11") (pintype "passive"))
      (node (ref "R90") (pin "48") (pinfunction "48_48") (pintype "passive"))
    )
    (net (code "89") (name "Net-(D318-Pad11)") (class "Default")
      (node (ref "D318") (pin "11") (pinfunction "11_11") (pintype "passive"))
      (node (ref "R91") (pin "48") (pinfunction "48_48") (pintype "passive"))
    )
    (net (code "90") (name "Net-(D319-Pad11)") (class "Default")
      (node (ref "D319") (pin "11") (pinfunction "11_11") (pintype "passive"))
      (node (ref "R92") (pin "48") (pinfunction "48_48") (pintype "passive"))
    )
    (net (code "91") (name "Net-(D320-Pad11)") (class "Default")
      (node (ref "D320") (pin "11") (pinfunction "11_11") (pintype "passive"))
      (node (ref "R93") (pin "48") (pinfunction "48_48") (pintype "passive"))
    )
    (net (code "92") (name "Net-(D321-Pad11)") (class "Default")
      (node (ref "D321") (pin "11") (pinfunction "11_11") (pintype "passive"))
      (node (ref "R94") (pin "48") (pinfunction "48_48") (pintype "passive"))
    )
    (net (code "93") (name "Net-(D322-Pad11)") (class "Default")
      (node (ref "D322") (pin "11") (pinfunction "11_11") (pintype "passive"))
      (node (ref "R95") (pin "48") (pinfunction "48_48") (pintype "passive"))
    )
  )
)
